# LPC1768.net
KiCad netlist of a schematic drawn in EAGLE
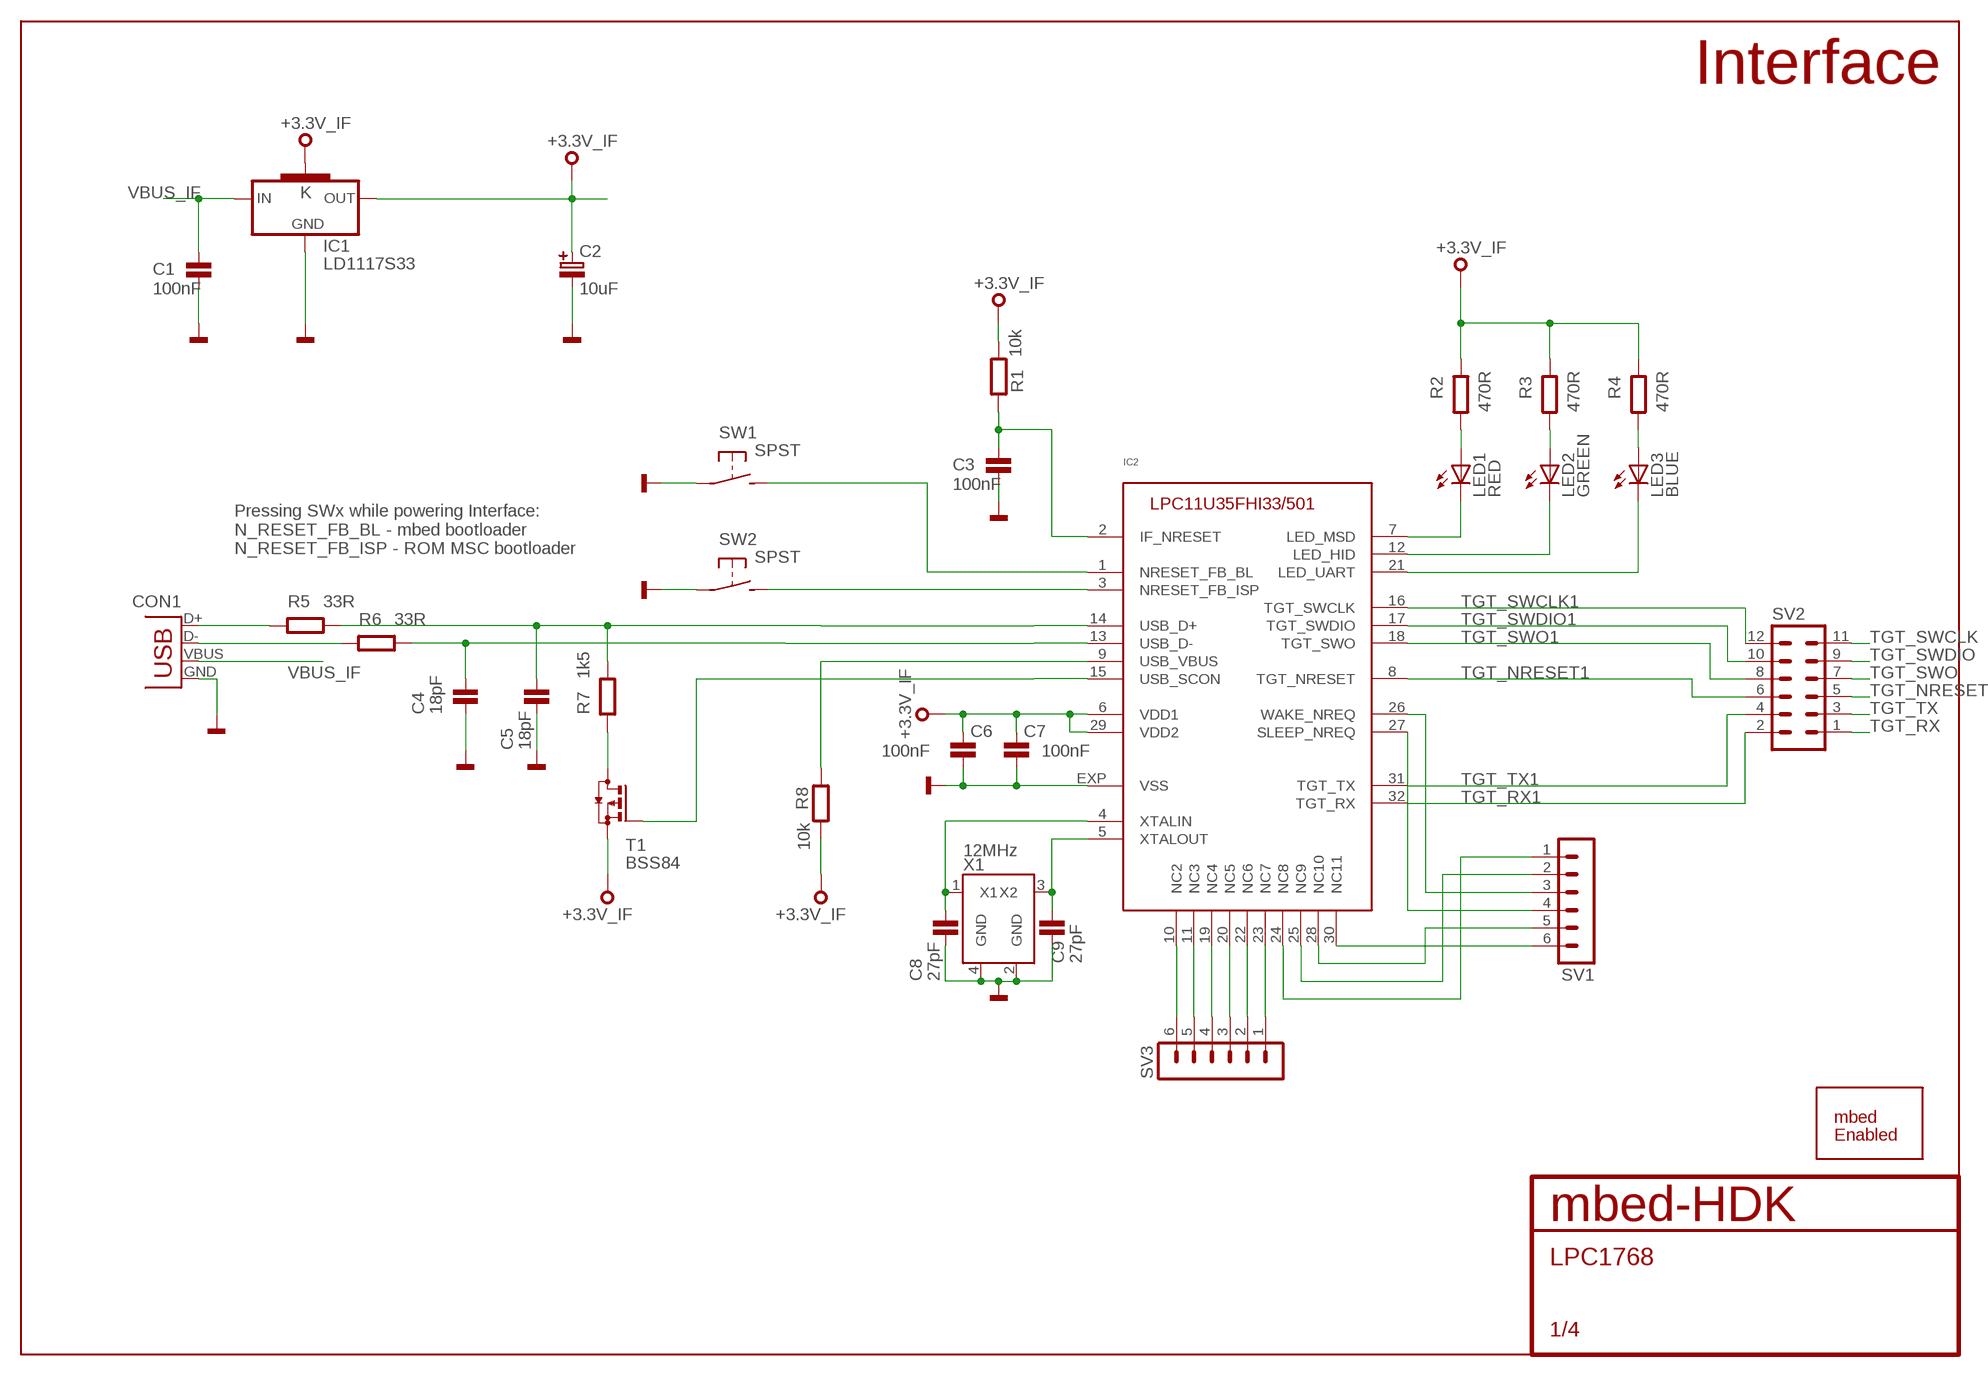
[diagram p0: schematic, sheet 1]
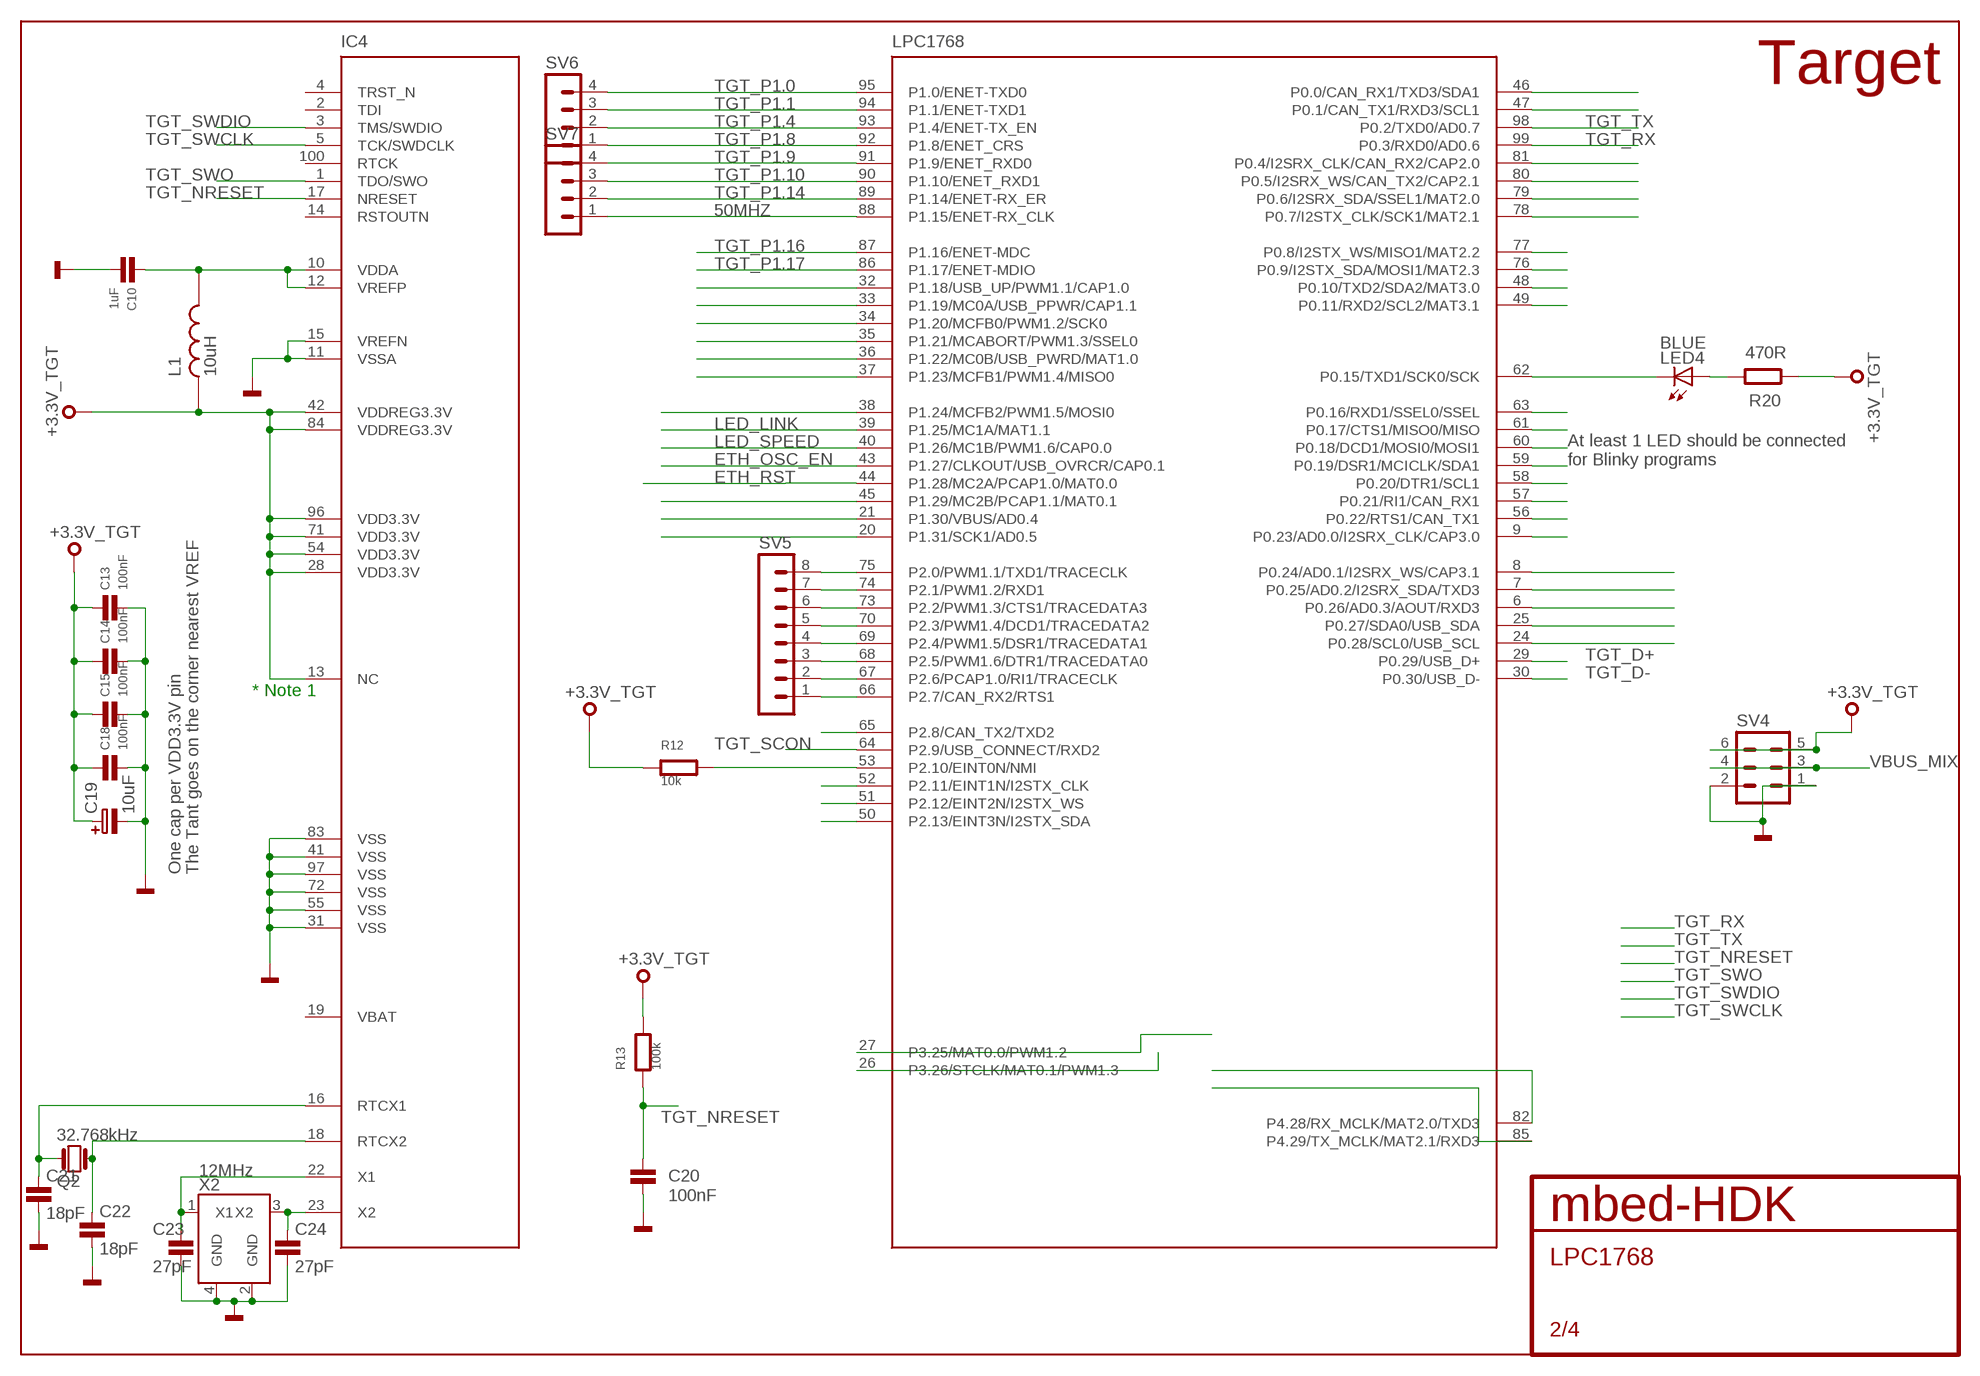
[diagram p1: schematic, sheet 2]
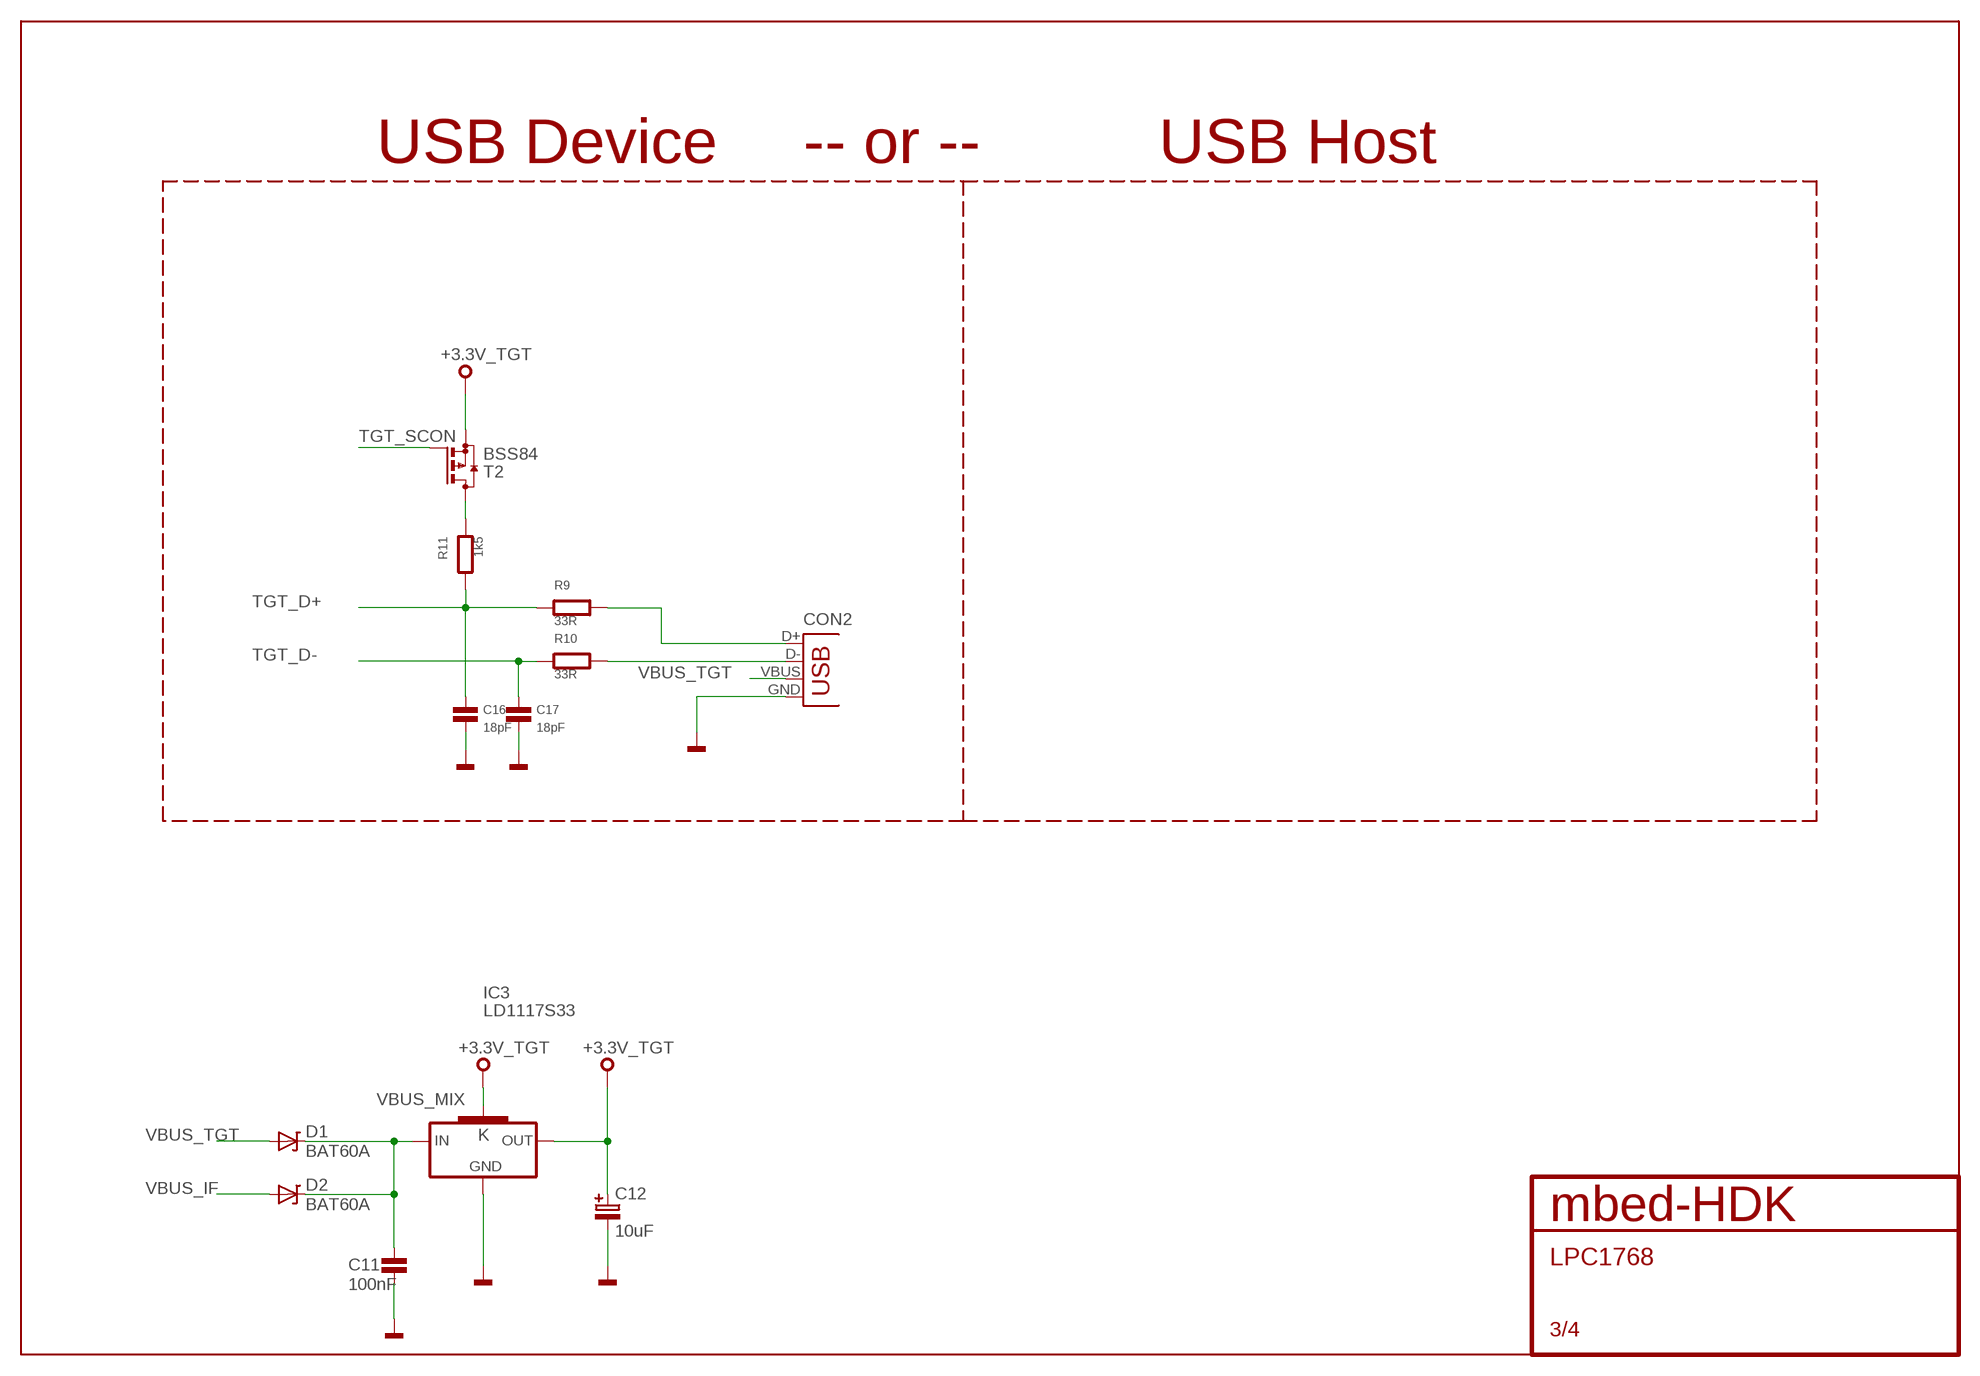
[diagram p2: schematic, sheet 3]
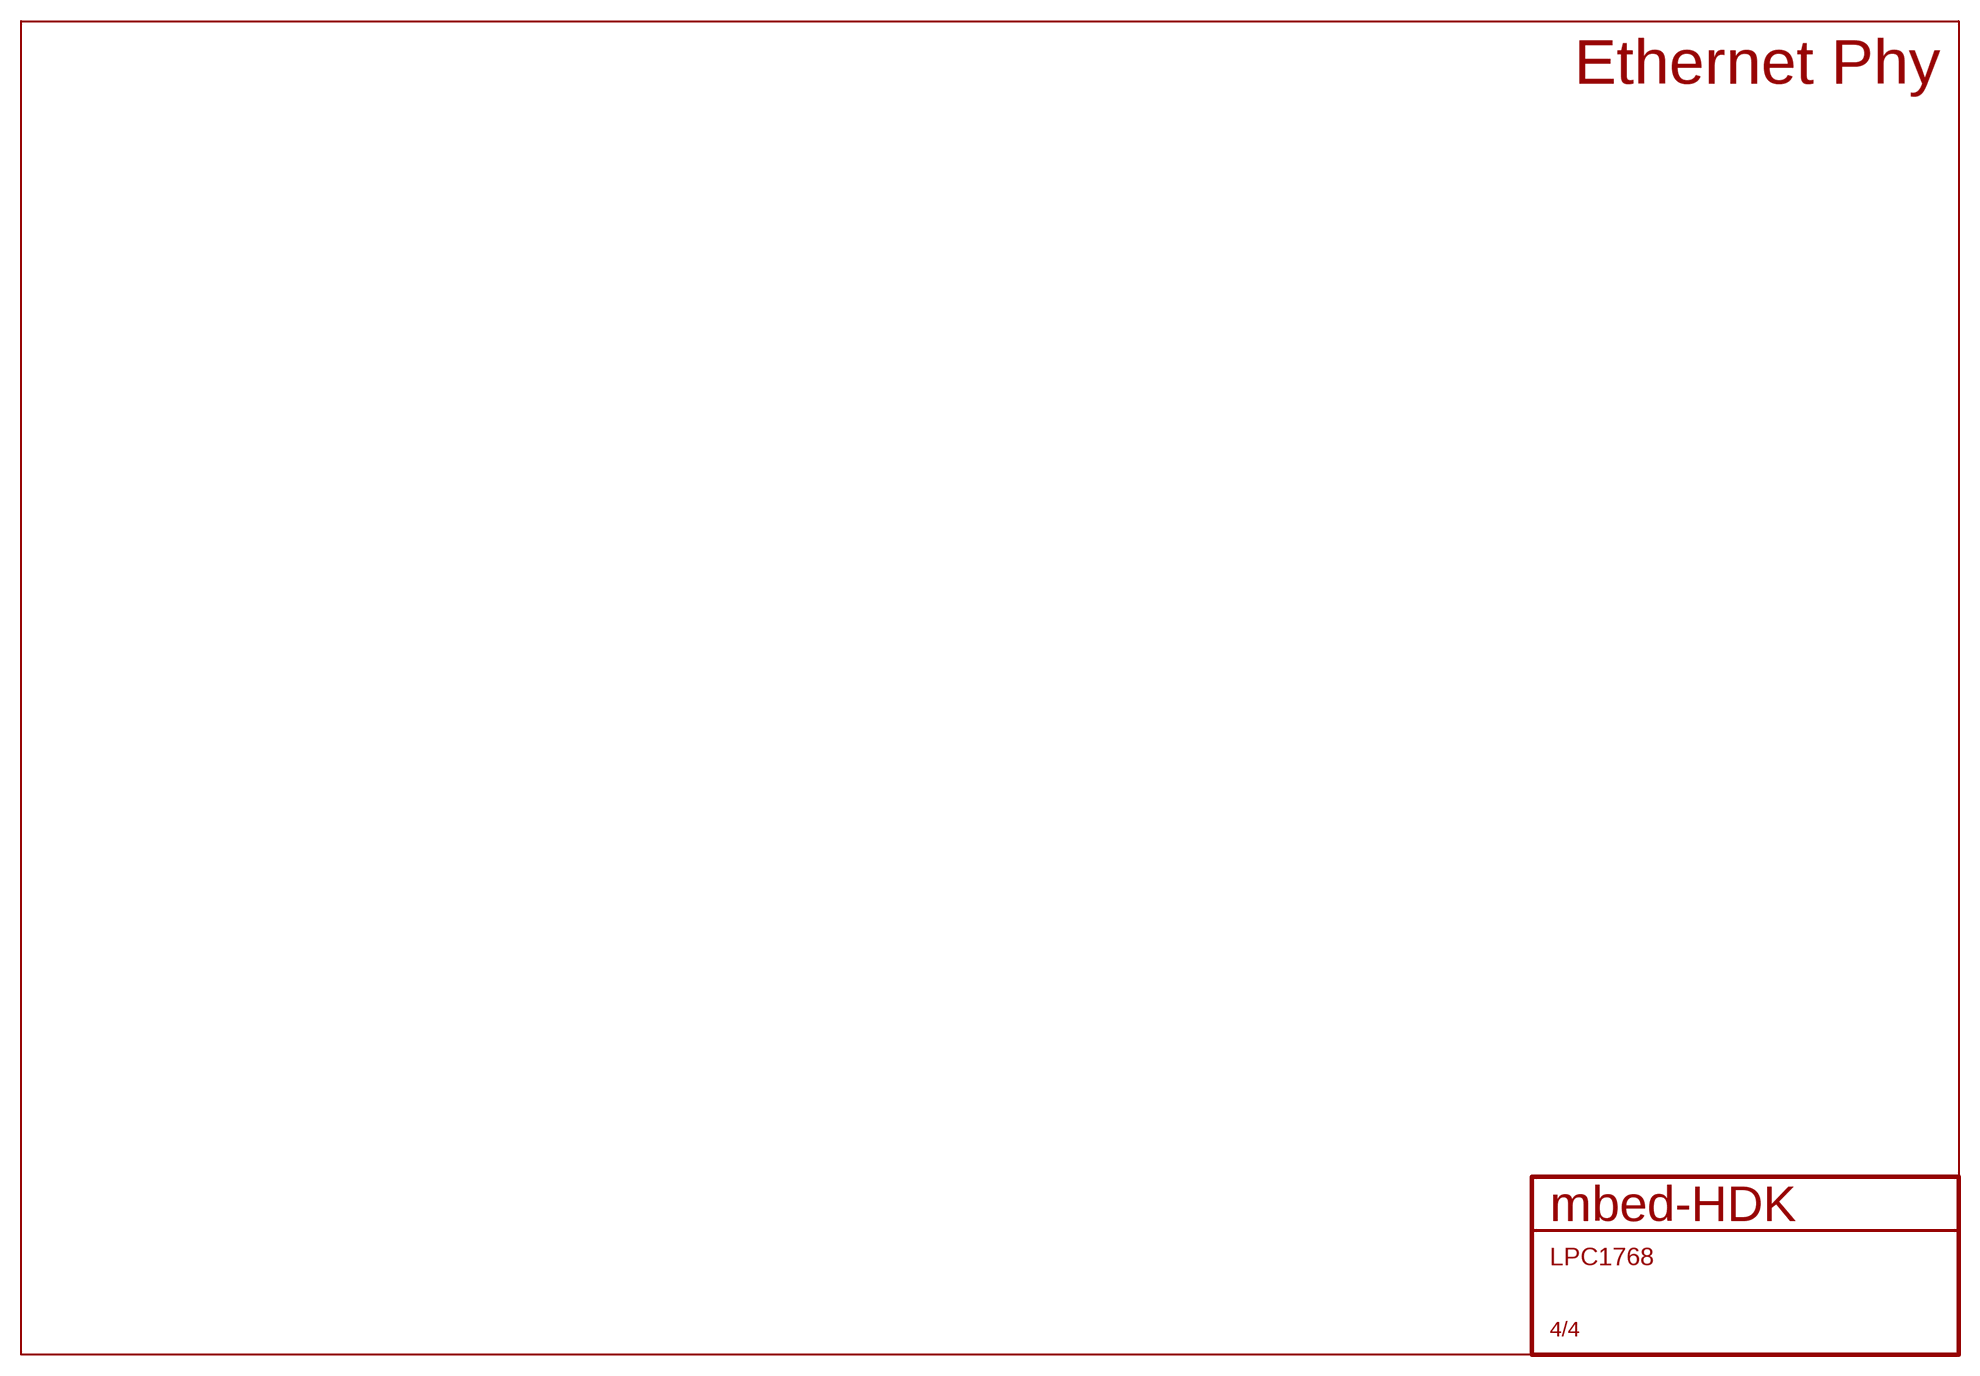
[diagram p3: schematic, sheet 4]

(export (version "E")
  (design (tool "Eeschema 10.0.6"))
  (components
    (comp (ref "C11")
      (value "100nF")
      (footprint "eagle-import:0603")
      (libsource (lib "eagle-import") (part "C0603"))
    )
    (comp (ref "C12")
      (value "10uF")
      (footprint "eagle-import:CASE-B")
      (libsource (lib "eagle-import") (part "C-POLB"))
    )
    (comp (ref "C16")
      (value "18pF")
      (footprint "eagle-import:0603")
      (libsource (lib "eagle-import") (part "C0603"))
    )
    (comp (ref "C17")
      (value "18pF")
      (footprint "eagle-import:0603")
      (libsource (lib "eagle-import") (part "C0603"))
    )
    (comp (ref "CON2")
      (value "USB-MB-S")
      (footprint "eagle-import:USB-MB-S")
      (libsource (lib "eagle-import") (part "USB-MB-S"))
    )
    (comp (ref "D1")
      (value "BAT60A")
      (footprint "eagle-import:BAT60A")
      (libsource (lib "eagle-import") (part "BAT60A"))
    )
    (comp (ref "D2")
      (value "BAT60A")
      (footprint "eagle-import:BAT60A")
      (libsource (lib "eagle-import") (part "BAT60A"))
    )
    (comp (ref "IC3")
      (value "LD1117S33")
      (footprint "eagle-import:SOT223")
      (libsource (lib "eagle-import") (part "LD1117S33"))
    )
    (comp (ref "R9")
      (value "33R")
      (footprint "eagle-import:0603")
      (libsource (lib "eagle-import") (part "R0603"))
    )
    (comp (ref "R10")
      (value "33R")
      (footprint "eagle-import:0603")
      (libsource (lib "eagle-import") (part "R0603"))
    )
    (comp (ref "R11")
      (value "1k5")
      (footprint "eagle-import:0603")
      (libsource (lib "eagle-import") (part "R0603"))
    )
    (comp (ref "T2")
      (value "BSS84")
      (footprint "eagle-import:SOT23")
      (libsource (lib "eagle-import") (part "BSS84"))
    )
    (comp (ref "C10")
      (value "1uF")
      (footprint "eagle-import:0603")
      (libsource (lib "eagle-import") (part "C0603"))
    )
    (comp (ref "C13")
      (value "100nF")
      (footprint "eagle-import:0603")
      (libsource (lib "eagle-import") (part "C0603"))
    )
    (comp (ref "C14")
      (value "100nF")
      (footprint "eagle-import:0603")
      (libsource (lib "eagle-import") (part "C0603"))
    )
    (comp (ref "C15")
      (value "100nF")
      (footprint "eagle-import:0603")
      (libsource (lib "eagle-import") (part "C0603"))
    )
    (comp (ref "C18")
      (value "100nF")
      (footprint "eagle-import:0603")
      (libsource (lib "eagle-import") (part "C0603"))
    )
    (comp (ref "C19")
      (value "10uF")
      (footprint "eagle-import:CASE-B")
      (libsource (lib "eagle-import") (part "C-POLB"))
    )
    (comp (ref "C20")
      (value "100nF")
      (footprint "eagle-import:0603")
      (libsource (lib "eagle-import") (part "C0603"))
    )
    (comp (ref "C21")
      (value "18pF")
      (footprint "eagle-import:0603")
      (libsource (lib "eagle-import") (part "C0603"))
    )
    (comp (ref "C22")
      (value "18pF")
      (footprint "eagle-import:0603")
      (libsource (lib "eagle-import") (part "C0603"))
    )
    (comp (ref "C23")
      (value "27pF")
      (footprint "eagle-import:0603")
      (libsource (lib "eagle-import") (part "C0603"))
    )
    (comp (ref "C24")
      (value "27pF")
      (footprint "eagle-import:0603")
      (libsource (lib "eagle-import") (part "C0603"))
    )
    (comp (ref "IC4")
      (value "LPC1768")
      (footprint "eagle-import:LQFP100")
      (libsource (lib "eagle-import") (part "LPC1768"))
    )
    (comp (ref "L1")
      (value "10uH")
      (footprint "eagle-import:0603")
      (libsource (lib "eagle-import") (part "L"))
    )
    (comp (ref "LED4")
      (value "BLUE")
      (footprint "eagle-import:CHIPLED_0603")
      (libsource (lib "eagle-import") (part "LED0603"))
    )
    (comp (ref "Q2")
      (value "32.768kHz")
      (footprint "eagle-import:FC135")
      (libsource (lib "eagle-import") (part "Q_FC135"))
    )
    (comp (ref "R12")
      (value "10k")
      (footprint "eagle-import:0603")
      (libsource (lib "eagle-import") (part "R0603"))
    )
    (comp (ref "R13")
      (value "100k")
      (footprint "eagle-import:0603")
      (libsource (lib "eagle-import") (part "R0603"))
    )
    (comp (ref "R20")
      (value "470R")
      (footprint "eagle-import:0603")
      (libsource (lib "eagle-import") (part "R0603"))
    )
    (comp (ref "SV4")
      (value "MA03-2")
      (footprint "eagle-import:MA03-2")
      (libsource (lib "eagle-import") (part "MA03-2"))
    )
    (comp (ref "SV5")
      (value "MA08-1")
      (footprint "eagle-import:MA08-1")
      (libsource (lib "eagle-import") (part "MA08-1"))
    )
    (comp (ref "SV6")
      (value "MA04-1")
      (footprint "eagle-import:MA04-1")
      (libsource (lib "eagle-import") (part "MA04-1"))
    )
    (comp (ref "SV7")
      (value "MA04-1")
      (footprint "eagle-import:MA04-1")
      (libsource (lib "eagle-import") (part "MA04-1"))
    )
    (comp (ref "X2")
      (value "12MHz")
      (footprint "eagle-import:OSC_CMD_32_25")
      (libsource (lib "eagle-import") (part "ABM8"))
    )
    (comp (ref "C1")
      (value "100nF")
      (footprint "eagle-import:0603")
      (libsource (lib "eagle-import") (part "C0603"))
    )
    (comp (ref "C2")
      (value "10uF")
      (footprint "eagle-import:CASE-B")
      (libsource (lib "eagle-import") (part "C-POLB"))
    )
    (comp (ref "C3")
      (value "100nF")
      (footprint "eagle-import:0603")
      (libsource (lib "eagle-import") (part "C0603"))
    )
    (comp (ref "C4")
      (value "18pF")
      (footprint "eagle-import:0603")
      (libsource (lib "eagle-import") (part "C0603"))
    )
    (comp (ref "C5")
      (value "18pF")
      (footprint "eagle-import:0603")
      (libsource (lib "eagle-import") (part "C0603"))
    )
    (comp (ref "C6")
      (value "100nF")
      (footprint "eagle-import:0603")
      (libsource (lib "eagle-import") (part "C0603"))
    )
    (comp (ref "C7")
      (value "100nF")
      (footprint "eagle-import:0603")
      (libsource (lib "eagle-import") (part "C0603"))
    )
    (comp (ref "C8")
      (value "27pF")
      (footprint "eagle-import:0603")
      (libsource (lib "eagle-import") (part "C0603"))
    )
    (comp (ref "C9")
      (value "27pF")
      (footprint "eagle-import:0603")
      (libsource (lib "eagle-import") (part "C0603"))
    )
    (comp (ref "CON1")
      (value "USB-MB-S")
      (footprint "eagle-import:USB-MB-S")
      (libsource (lib "eagle-import") (part "USB-MB-S"))
    )
    (comp (ref "IC1")
      (value "LD1117S33")
      (footprint "eagle-import:SOT223")
      (libsource (lib "eagle-import") (part "LD1117S33"))
    )
    (comp (ref "IC2")
      (value "IF-LPC11U35")
      (footprint "eagle-import:HVQFN33")
      (libsource (lib "eagle-import") (part "IF-LPC11U35"))
    )
    (comp (ref "LED1")
      (value "RED")
      (footprint "eagle-import:CHIPLED_0603")
      (libsource (lib "eagle-import") (part "LED0603"))
    )
    (comp (ref "LED2")
      (value "GREEN")
      (footprint "eagle-import:CHIPLED_0603")
      (libsource (lib "eagle-import") (part "LED0603"))
    )
    (comp (ref "LED3")
      (value "BLUE")
      (footprint "eagle-import:CHIPLED_0603")
      (libsource (lib "eagle-import") (part "LED0603"))
    )
    (comp (ref "R1")
      (value "10k")
      (footprint "eagle-import:0603")
      (libsource (lib "eagle-import") (part "R0603"))
    )
    (comp (ref "R2")
      (value "470R")
      (footprint "eagle-import:0603")
      (libsource (lib "eagle-import") (part "R0603"))
    )
    (comp (ref "R3")
      (value "470R")
      (footprint "eagle-import:0603")
      (libsource (lib "eagle-import") (part "R0603"))
    )
    (comp (ref "R4")
      (value "470R")
      (footprint "eagle-import:0603")
      (libsource (lib "eagle-import") (part "R0603"))
    )
    (comp (ref "R5")
      (value "33R")
      (footprint "eagle-import:0603")
      (libsource (lib "eagle-import") (part "R0603"))
    )
    (comp (ref "R6")
      (value "33R")
      (footprint "eagle-import:0603")
      (libsource (lib "eagle-import") (part "R0603"))
    )
    (comp (ref "R7")
      (value "1k5")
      (footprint "eagle-import:0603")
      (libsource (lib "eagle-import") (part "R0603"))
    )
    (comp (ref "R8")
      (value "10k")
      (footprint "eagle-import:0603")
      (libsource (lib "eagle-import") (part "R0603"))
    )
    (comp (ref "SS1")
      (value "MBED-ENABLED-LOGOMEDIUM")
      (footprint "eagle-import:MBED-ENABLED-LOGO-500X500-MIL")
      (libsource (lib "eagle-import") (part "MBED-ENABLED-LOGOMEDIUM"))
    )
    (comp (ref "SV1")
      (value "MA06-1")
      (footprint "eagle-import:MA06-1")
      (libsource (lib "eagle-import") (part "MA06-1"))
    )
    (comp (ref "SV2")
      (value "MA06-2")
      (footprint "eagle-import:MA06-2")
      (libsource (lib "eagle-import") (part "MA06-2"))
    )
    (comp (ref "SV3")
      (value "MA06-1")
      (footprint "eagle-import:MA06-1")
      (libsource (lib "eagle-import") (part "MA06-1"))
    )
    (comp (ref "SW1")
      (value "SPST")
      (footprint "eagle-import:DTSM-32S-B")
      (libsource (lib "eagle-import") (part "SPST"))
    )
    (comp (ref "SW2")
      (value "SPST")
      (footprint "eagle-import:DTSM-32S-B")
      (libsource (lib "eagle-import") (part "SPST"))
    )
    (comp (ref "T1")
      (value "BSS84")
      (footprint "eagle-import:SOT23")
      (libsource (lib "eagle-import") (part "BSS84"))
    )
    (comp (ref "X1")
      (value "12MHz")
      (footprint "eagle-import:OSC_CMD_32_25")
      (libsource (lib "eagle-import") (part "ABM8"))
    )
  )
  (nets
    (net (code "1") (name "+3.3V_IF") (class "Default")
      (node (ref "C2") (pin "1") (pinfunction "1_1") (pintype "passive"))
      (node (ref "C6") (pin "1") (pinfunction "P$1_1") (pintype "passive"))
      (node (ref "C7") (pin "1") (pinfunction "P$1_1") (pintype "passive"))
      (node (ref "IC1") (pin "2") (pinfunction "OUT_2") (pintype "passive"))
      (node (ref "IC1") (pin "4") (pinfunction "K_4") (pintype "passive"))
      (node (ref "IC2") (pin "29") (pinfunction "VDD2_29") (pintype "bidirectional"))
      (node (ref "IC2") (pin "6") (pinfunction "VDD1_6") (pintype "bidirectional"))
      (node (ref "R1") (pin "2") (pinfunction "P$2_2") (pintype "passive"))
      (node (ref "R2") (pin "1") (pinfunction "P$1_1") (pintype "passive"))
      (node (ref "R3") (pin "1") (pinfunction "P$1_1") (pintype "passive"))
      (node (ref "R4") (pin "1") (pinfunction "P$1_1") (pintype "passive"))
      (node (ref "R8") (pin "2") (pinfunction "P$2_2") (pintype "passive"))
      (node (ref "T1") (pin "2") (pinfunction "S_2") (pintype "passive"))
    )
    (net (code "2") (name "+3.3V_TGT") (class "Default")
      (node (ref "C12") (pin "1") (pinfunction "1_1") (pintype "passive"))
      (node (ref "C13") (pin "1") (pinfunction "P$1_1") (pintype "passive"))
      (node (ref "C14") (pin "1") (pinfunction "P$1_1") (pintype "passive"))
      (node (ref "C15") (pin "1") (pinfunction "P$1_1") (pintype "passive"))
      (node (ref "C18") (pin "1") (pinfunction "P$1_1") (pintype "passive"))
      (node (ref "C19") (pin "1") (pinfunction "1_1") (pintype "passive"))
      (node (ref "IC3") (pin "2") (pinfunction "OUT_2") (pintype "passive"))
      (node (ref "IC3") (pin "4") (pinfunction "K_4") (pintype "passive"))
      (node (ref "IC4") (pin "13") (pinfunction "NC_13") (pintype "bidirectional"))
      (node (ref "IC4") (pin "28") (pinfunction "VDD3.3V_28") (pintype "bidirectional"))
      (node (ref "IC4") (pin "42") (pinfunction "VDDREG3.3V_42") (pintype "bidirectional"))
      (node (ref "IC4") (pin "54") (pinfunction "VDD3.3V_54") (pintype "bidirectional"))
      (node (ref "IC4") (pin "71") (pinfunction "VDD3.3V_71") (pintype "bidirectional"))
      (node (ref "IC4") (pin "84") (pinfunction "VDDREG3.3V_84") (pintype "bidirectional"))
      (node (ref "IC4") (pin "96") (pinfunction "VDD3.3V_96") (pintype "bidirectional"))
      (node (ref "L1") (pin "1") (pinfunction "P$1_1") (pintype "bidirectional"))
      (node (ref "R12") (pin "1") (pinfunction "P$1_1") (pintype "passive"))
      (node (ref "R13") (pin "2") (pinfunction "P$2_2") (pintype "passive"))
      (node (ref "R20") (pin "1") (pinfunction "P$1_1") (pintype "passive"))
      (node (ref "SV4") (pin "5") (pinfunction "5_5") (pintype "passive"))
      (node (ref "SV4") (pin "6") (pinfunction "6_6") (pintype "passive"))
      (node (ref "T2") (pin "2") (pinfunction "S_2") (pintype "passive"))
    )
    (net (code "3") (name "50MHZ") (class "Default")
      (node (ref "IC4") (pin "88") (pinfunction "P1.15/ENET-RX_CLK_88") (pintype "bidirectional"))
      (node (ref "SV7") (pin "1") (pinfunction "1_1") (pintype "passive"))
    )
    (net (code "4") (name "ETH_OSC_EN") (class "Default")
      (node (ref "IC4") (pin "43") (pinfunction "P1.27/CLKOUT/USB_OVRCR/CAP0.1_43") (pintype "bidirectional"))
    )
    (net (code "5") (name "ETH_RST") (class "Default")
      (node (ref "IC4") (pin "44") (pinfunction "P1.28/MC2A/PCAP1.0/MAT0.0_44") (pintype "bidirectional"))
    )
    (net (code "6") (name "GND") (class "Default")
      (node (ref "C1") (pin "2") (pinfunction "P$2_2") (pintype "passive"))
      (node (ref "C10") (pin "2") (pinfunction "P$2_2") (pintype "passive"))
      (node (ref "C11") (pin "2") (pinfunction "P$2_2") (pintype "passive"))
      (node (ref "C12") (pin "2") (pinfunction "2_2") (pintype "passive"))
      (node (ref "C13") (pin "2") (pinfunction "P$2_2") (pintype "passive"))
      (node (ref "C14") (pin "2") (pinfunction "P$2_2") (pintype "passive"))
      (node (ref "C15") (pin "2") (pinfunction "P$2_2") (pintype "passive"))
      (node (ref "C16") (pin "2") (pinfunction "P$2_2") (pintype "passive"))
      (node (ref "C17") (pin "2") (pinfunction "P$2_2") (pintype "passive"))
      (node (ref "C18") (pin "2") (pinfunction "P$2_2") (pintype "passive"))
      (node (ref "C19") (pin "2") (pinfunction "2_2") (pintype "passive"))
      (node (ref "C2") (pin "2") (pinfunction "2_2") (pintype "passive"))
      (node (ref "C20") (pin "1") (pinfunction "P$1_1") (pintype "passive"))
      (node (ref "C21") (pin "1") (pinfunction "P$1_1") (pintype "passive"))
      (node (ref "C22") (pin "1") (pinfunction "P$1_1") (pintype "passive"))
      (node (ref "C23") (pin "1") (pinfunction "P$1_1") (pintype "passive"))
      (node (ref "C24") (pin "1") (pinfunction "P$1_1") (pintype "passive"))
      (node (ref "C3") (pin "2") (pinfunction "P$2_2") (pintype "passive"))
      (node (ref "C4") (pin "2") (pinfunction "P$2_2") (pintype "passive"))
      (node (ref "C5") (pin "2") (pinfunction "P$2_2") (pintype "passive"))
      (node (ref "C6") (pin "2") (pinfunction "P$2_2") (pintype "passive"))
      (node (ref "C7") (pin "2") (pinfunction "P$2_2") (pintype "passive"))
      (node (ref "C8") (pin "2") (pinfunction "P$2_2") (pintype "passive"))
      (node (ref "C9") (pin "2") (pinfunction "P$2_2") (pintype "passive"))
      (node (ref "CON1") (pin "GND") (pinfunction "GND_GND") (pintype "bidirectional"))
      (node (ref "CON2") (pin "GND") (pinfunction "GND_GND") (pintype "bidirectional"))
      (node (ref "IC1") (pin "1") (pinfunction "GND_1") (pintype "input"))
      (node (ref "IC2") (pin "EXP") (pinfunction "VSS_EXP") (pintype "bidirectional"))
      (node (ref "IC3") (pin "1") (pinfunction "GND_1") (pintype "input"))
      (node (ref "IC4") (pin "11") (pinfunction "VSSA_11") (pintype "bidirectional"))
      (node (ref "IC4") (pin "15") (pinfunction "VREFN_15") (pintype "bidirectional"))
      (node (ref "IC4") (pin "31") (pinfunction "VSS_31") (pintype "bidirectional"))
      (node (ref "IC4") (pin "41") (pinfunction "VSS_41") (pintype "bidirectional"))
      (node (ref "IC4") (pin "55") (pinfunction "VSS_55") (pintype "bidirectional"))
      (node (ref "IC4") (pin "72") (pinfunction "VSS_72") (pintype "bidirectional"))
      (node (ref "IC4") (pin "83") (pinfunction "VSS_83") (pintype "bidirectional"))
      (node (ref "IC4") (pin "97") (pinfunction "VSS_97") (pintype "bidirectional"))
      (node (ref "SV4") (pin "1") (pinfunction "1_1") (pintype "passive"))
      (node (ref "SV4") (pin "2") (pinfunction "2_2") (pintype "passive"))
      (node (ref "SW1") (pin "P$1") (pinfunction "P_P$1") (pintype "passive"))
      (node (ref "SW2") (pin "P$1") (pinfunction "P_P$1") (pintype "passive"))
      (node (ref "X1") (pin "2") (pinfunction "GND_2") (pintype "bidirectional"))
      (node (ref "X1") (pin "4") (pinfunction "GND_4") (pintype "bidirectional"))
      (node (ref "X2") (pin "2") (pinfunction "GND_2") (pintype "bidirectional"))
      (node (ref "X2") (pin "4") (pinfunction "GND_4") (pintype "bidirectional"))
    )
    (net (code "7") (name "LED_LINK") (class "Default")
      (node (ref "IC4") (pin "39") (pinfunction "P1.25/MC1A/MAT1.1_39") (pintype "bidirectional"))
    )
    (net (code "8") (name "LED_SPEED") (class "Default")
      (node (ref "IC4") (pin "40") (pinfunction "P1.26/MC1B/PWM1.6/CAP0.0_40") (pintype "bidirectional"))
    )
    (net (code "9") (name "Net-(C3-P$1)") (class "Default")
      (node (ref "C3") (pin "1") (pinfunction "P$1_1") (pintype "passive"))
      (node (ref "IC2") (pin "2") (pinfunction "IF_NRESET_2") (pintype "bidirectional"))
      (node (ref "R1") (pin "1") (pinfunction "P$1_1") (pintype "passive"))
    )
    (net (code "10") (name "Net-(C4-P$1)") (class "Default")
      (node (ref "C4") (pin "1") (pinfunction "P$1_1") (pintype "passive"))
      (node (ref "IC2") (pin "13") (pinfunction "USB_D-_13") (pintype "bidirectional"))
      (node (ref "R6") (pin "2") (pinfunction "P$2_2") (pintype "passive"))
    )
    (net (code "11") (name "Net-(C5-P$1)") (class "Default")
      (node (ref "C5") (pin "1") (pinfunction "P$1_1") (pintype "passive"))
      (node (ref "IC2") (pin "14") (pinfunction "USB_D+_14") (pintype "bidirectional"))
      (node (ref "R5") (pin "2") (pinfunction "P$2_2") (pintype "passive"))
      (node (ref "R7") (pin "2") (pinfunction "P$2_2") (pintype "passive"))
    )
    (net (code "12") (name "Net-(C8-P$1)") (class "Default")
      (node (ref "C8") (pin "1") (pinfunction "P$1_1") (pintype "passive"))
      (node (ref "IC2") (pin "4") (pinfunction "XTALIN_4") (pintype "bidirectional"))
      (node (ref "X1") (pin "1") (pinfunction "X1_1") (pintype "bidirectional"))
    )
    (net (code "13") (name "Net-(C9-P$1)") (class "Default")
      (node (ref "C9") (pin "1") (pinfunction "P$1_1") (pintype "passive"))
      (node (ref "IC2") (pin "5") (pinfunction "XTALOUT_5") (pintype "bidirectional"))
      (node (ref "X1") (pin "3") (pinfunction "X2_3") (pintype "bidirectional"))
    )
    (net (code "14") (name "Net-(C10-P$1)") (class "Default")
      (node (ref "C10") (pin "1") (pinfunction "P$1_1") (pintype "passive"))
      (node (ref "IC4") (pin "10") (pinfunction "VDDA_10") (pintype "bidirectional"))
      (node (ref "IC4") (pin "12") (pinfunction "VREFP_12") (pintype "bidirectional"))
      (node (ref "L1") (pin "2") (pinfunction "P$2_2") (pintype "bidirectional"))
    )
    (net (code "15") (name "Net-(C21-P$2)") (class "Default")
      (node (ref "C21") (pin "2") (pinfunction "P$2_2") (pintype "passive"))
      (node (ref "IC4") (pin "16") (pinfunction "RTCX1_16") (pintype "bidirectional"))
      (node (ref "Q2") (pin "X2") (pinfunction "2_X2") (pintype "passive"))
    )
    (net (code "16") (name "Net-(C22-P$2)") (class "Default")
      (node (ref "C22") (pin "2") (pinfunction "P$2_2") (pintype "passive"))
      (node (ref "IC4") (pin "18") (pinfunction "RTCX2_18") (pintype "bidirectional"))
      (node (ref "Q2") (pin "X1") (pinfunction "1_X1") (pintype "passive"))
    )
    (net (code "17") (name "Net-(C23-P$2)") (class "Default")
      (node (ref "C23") (pin "2") (pinfunction "P$2_2") (pintype "passive"))
      (node (ref "IC4") (pin "22") (pinfunction "X1_22") (pintype "bidirectional"))
      (node (ref "X2") (pin "1") (pinfunction "X1_1") (pintype "bidirectional"))
    )
    (net (code "18") (name "Net-(C24-P$2)") (class "Default")
      (node (ref "C24") (pin "2") (pinfunction "P$2_2") (pintype "passive"))
      (node (ref "IC4") (pin "23") (pinfunction "X2_23") (pintype "bidirectional"))
      (node (ref "X2") (pin "3") (pinfunction "X2_3") (pintype "bidirectional"))
    )
    (net (code "19") (name "Net-(IC2-LED_HID)") (class "Default")
      (node (ref "IC2") (pin "12") (pinfunction "LED_HID_12") (pintype "bidirectional"))
      (node (ref "LED2") (pin "C") (pinfunction "C_C") (pintype "passive"))
    )
    (net (code "20") (name "Net-(IC2-LED_MSD)") (class "Default")
      (node (ref "IC2") (pin "7") (pinfunction "LED_MSD_7") (pintype "bidirectional"))
      (node (ref "LED1") (pin "C") (pinfunction "C_C") (pintype "passive"))
    )
    (net (code "21") (name "Net-(IC2-LED_UART)") (class "Default")
      (node (ref "IC2") (pin "21") (pinfunction "LED_UART_21") (pintype "bidirectional"))
      (node (ref "LED3") (pin "C") (pinfunction "C_C") (pintype "passive"))
    )
    (net (code "22") (name "Net-(IC2-NC2)") (class "Default")
      (node (ref "IC2") (pin "10") (pinfunction "NC2_10") (pintype "bidirectional"))
      (node (ref "SV3") (pin "6") (pinfunction "6_6") (pintype "passive"))
    )
    (net (code "23") (name "Net-(IC2-NC3)") (class "Default")
      (node (ref "IC2") (pin "11") (pinfunction "NC3_11") (pintype "bidirectional"))
      (node (ref "SV3") (pin "5") (pinfunction "5_5") (pintype "passive"))
    )
    (net (code "24") (name "Net-(IC2-NC4)") (class "Default")
      (node (ref "IC2") (pin "19") (pinfunction "NC4_19") (pintype "bidirectional"))
      (node (ref "SV3") (pin "4") (pinfunction "4_4") (pintype "passive"))
    )
    (net (code "25") (name "Net-(IC2-NC5)") (class "Default")
      (node (ref "IC2") (pin "20") (pinfunction "NC5_20") (pintype "bidirectional"))
      (node (ref "SV3") (pin "3") (pinfunction "3_3") (pintype "passive"))
    )
    (net (code "26") (name "Net-(IC2-NC6)") (class "Default")
      (node (ref "IC2") (pin "22") (pinfunction "NC6_22") (pintype "bidirectional"))
      (node (ref "SV3") (pin "2") (pinfunction "2_2") (pintype "passive"))
    )
    (net (code "27") (name "Net-(IC2-NC7)") (class "Default")
      (node (ref "IC2") (pin "23") (pinfunction "NC7_23") (pintype "bidirectional"))
      (node (ref "SV3") (pin "1") (pinfunction "1_1") (pintype "passive"))
    )
    (net (code "28") (name "Net-(IC2-NC8)") (class "Default")
      (node (ref "IC2") (pin "24") (pinfunction "NC8_24") (pintype "bidirectional"))
      (node (ref "SV1") (pin "1") (pinfunction "1_1") (pintype "passive"))
    )
    (net (code "29") (name "Net-(IC2-NC9)") (class "Default")
      (node (ref "IC2") (pin "25") (pinfunction "NC9_25") (pintype "bidirectional"))
      (node (ref "SV1") (pin "2") (pinfunction "2_2") (pintype "passive"))
    )
    (net (code "30") (name "Net-(IC2-NC10)") (class "Default")
      (node (ref "IC2") (pin "28") (pinfunction "NC10_28") (pintype "bidirectional"))
      (node (ref "SV1") (pin "5") (pinfunction "5_5") (pintype "passive"))
    )
    (net (code "31") (name "Net-(IC2-NC11)") (class "Default")
      (node (ref "IC2") (pin "30") (pinfunction "NC11_30") (pintype "bidirectional"))
      (node (ref "SV1") (pin "6") (pinfunction "6_6") (pintype "passive"))
    )
    (net (code "32") (name "Net-(IC2-NRESET_FB_BL)") (class "Default")
      (node (ref "IC2") (pin "1") (pinfunction "NRESET_FB_BL_1") (pintype "bidirectional"))
      (node (ref "SW1") (pin "P$2") (pinfunction "S_P$2") (pintype "passive"))
    )
    (net (code "33") (name "Net-(IC2-NRESET_FB_ISP)") (class "Default")
      (node (ref "IC2") (pin "3") (pinfunction "NRESET_FB_ISP_3") (pintype "bidirectional"))
      (node (ref "SW2") (pin "P$2") (pinfunction "S_P$2") (pintype "passive"))
    )
    (net (code "34") (name "Net-(IC2-SLEEP_NREQ)") (class "Default")
      (node (ref "IC2") (pin "27") (pinfunction "SLEEP_NREQ_27") (pintype "bidirectional"))
      (node (ref "SV1") (pin "4") (pinfunction "4_4") (pintype "passive"))
    )
    (net (code "35") (name "Net-(IC2-USB_SCON)") (class "Default")
      (node (ref "IC2") (pin "15") (pinfunction "USB_SCON_15") (pintype "bidirectional"))
      (node (ref "T1") (pin "1") (pinfunction "G_1") (pintype "passive"))
    )
    (net (code "36") (name "Net-(IC2-USB_VBUS)") (class "Default")
      (node (ref "IC2") (pin "9") (pinfunction "USB_VBUS_9") (pintype "bidirectional"))
      (node (ref "R8") (pin "1") (pinfunction "P$1_1") (pintype "passive"))
    )
    (net (code "37") (name "Net-(IC2-WAKE_NREQ)") (class "Default")
      (node (ref "IC2") (pin "26") (pinfunction "WAKE_NREQ_26") (pintype "bidirectional"))
      (node (ref "SV1") (pin "3") (pinfunction "3_3") (pintype "passive"))
    )
    (net (code "38") (name "Net-(IC4-P0.15{slash}TXD1{slash}SCK0{slash}SCK)") (class "Default")
      (node (ref "IC4") (pin "62") (pinfunction "P0.15/TXD1/SCK0/SCK_62") (pintype "bidirectional"))
      (node (ref "LED4") (pin "C") (pinfunction "C_C") (pintype "passive"))
    )
    (net (code "39") (name "Net-(IC4-P2.0{slash}PWM1.1{slash}TXD1{slash}TRACECLK)") (class "Default")
      (node (ref "IC4") (pin "75") (pinfunction "P2.0/PWM1.1/TXD1/TRACECLK_75") (pintype "bidirectional"))
      (node (ref "SV5") (pin "8") (pinfunction "8_8") (pintype "passive"))
    )
    (net (code "40") (name "Net-(IC4-P2.1{slash}PWM1.2{slash}RXD1)") (class "Default")
      (node (ref "IC4") (pin "74") (pinfunction "P2.1/PWM1.2/RXD1_74") (pintype "bidirectional"))
      (node (ref "SV5") (pin "7") (pinfunction "7_7") (pintype "passive"))
    )
    (net (code "41") (name "Net-(IC4-P2.2{slash}PWM1.3{slash}CTS1{slash}TRACEDATA3)") (class "Default")
      (node (ref "IC4") (pin "73") (pinfunction "P2.2/PWM1.3/CTS1/TRACEDATA3_73") (pintype "bidirectional"))
      (node (ref "SV5") (pin "6") (pinfunction "6_6") (pintype "passive"))
    )
    (net (code "42") (name "Net-(IC4-P2.3{slash}PWM1.4{slash}DCD1{slash}TRACEDATA2)") (class "Default")
      (node (ref "IC4") (pin "70") (pinfunction "P2.3/PWM1.4/DCD1/TRACEDATA2_70") (pintype "bidirectional"))
      (node (ref "SV5") (pin "5") (pinfunction "5_5") (pintype "passive"))
    )
    (net (code "43") (name "Net-(IC4-P2.4{slash}PWM1.5{slash}DSR1{slash}TRACEDATA1)") (class "Default")
      (node (ref "IC4") (pin "69") (pinfunction "P2.4/PWM1.5/DSR1/TRACEDATA1_69") (pintype "bidirectional"))
      (node (ref "SV5") (pin "4") (pinfunction "4_4") (pintype "passive"))
    )
    (net (code "44") (name "Net-(IC4-P2.5{slash}PWM1.6{slash}DTR1{slash}TRACEDATA0)") (class "Default")
      (node (ref "IC4") (pin "68") (pinfunction "P2.5/PWM1.6/DTR1/TRACEDATA0_68") (pintype "bidirectional"))
      (node (ref "SV5") (pin "3") (pinfunction "3_3") (pintype "passive"))
    )
    (net (code "45") (name "Net-(IC4-P2.6{slash}PCAP1.0{slash}RI1{slash}TRACECLK)") (class "Default")
      (node (ref "IC4") (pin "67") (pinfunction "P2.6/PCAP1.0/RI1/TRACECLK_67") (pintype "bidirectional"))
      (node (ref "SV5") (pin "2") (pinfunction "2_2") (pintype "passive"))
    )
    (net (code "46") (name "Net-(IC4-P2.7{slash}CAN_RX2{slash}RTS1)") (class "Default")
      (node (ref "IC4") (pin "66") (pinfunction "P2.7/CAN_RX2/RTS1_66") (pintype "bidirectional"))
      (node (ref "SV5") (pin "1") (pinfunction "1_1") (pintype "passive"))
    )
    (net (code "47") (name "Net-(IC4-P2.10{slash}EINT0N{slash}NMI)") (class "Default")
      (node (ref "IC4") (pin "53") (pinfunction "P2.10/EINT0N/NMI_53") (pintype "bidirectional"))
      (node (ref "R12") (pin "2") (pinfunction "P$2_2") (pintype "passive"))
    )
    (net (code "48") (name "Net-(R2-P$2)") (class "Default")
      (node (ref "LED1") (pin "A") (pinfunction "A_A") (pintype "passive"))
      (node (ref "R2") (pin "2") (pinfunction "P$2_2") (pintype "passive"))
    )
    (net (code "49") (name "Net-(R3-P$2)") (class "Default")
      (node (ref "LED2") (pin "A") (pinfunction "A_A") (pintype "passive"))
      (node (ref "R3") (pin "2") (pinfunction "P$2_2") (pintype "passive"))
    )
    (net (code "50") (name "Net-(R4-P$2)") (class "Default")
      (node (ref "LED3") (pin "A") (pinfunction "A_A") (pintype "passive"))
      (node (ref "R4") (pin "2") (pinfunction "P$2_2") (pintype "passive"))
    )
    (net (code "51") (name "Net-(R5-P$1)") (class "Default")
      (node (ref "CON1") (pin "D+") (pinfunction "D+_D+") (pintype "bidirectional"))
      (node (ref "R5") (pin "1") (pinfunction "P$1_1") (pintype "passive"))
    )
    (net (code "52") (name "Net-(R6-P$1)") (class "Default")
      (node (ref "CON1") (pin "D-") (pinfunction "D-_D-") (pintype "bidirectional"))
      (node (ref "R6") (pin "1") (pinfunction "P$1_1") (pintype "passive"))
    )
    (net (code "53") (name "Net-(R7-P$1)") (class "Default")
      (node (ref "R7") (pin "1") (pinfunction "P$1_1") (pintype "passive"))
      (node (ref "T1") (pin "3") (pinfunction "D_3") (pintype "passive"))
    )
    (net (code "54") (name "Net-(R9-P$2)") (class "Default")
      (node (ref "CON2") (pin "D+") (pinfunction "D+_D+") (pintype "bidirectional"))
      (node (ref "R9") (pin "2") (pinfunction "P$2_2") (pintype "passive"))
    )
    (net (code "55") (name "Net-(R10-P$2)") (class "Default")
      (node (ref "CON2") (pin "D-") (pinfunction "D-_D-") (pintype "bidirectional"))
      (node (ref "R10") (pin "2") (pinfunction "P$2_2") (pintype "passive"))
    )
    (net (code "56") (name "Net-(R11-P$1)") (class "Default")
      (node (ref "R11") (pin "1") (pinfunction "P$1_1") (pintype "passive"))
      (node (ref "T2") (pin "3") (pinfunction "D_3") (pintype "passive"))
    )
    (net (code "57") (name "Net-(R20-P$2)") (class "Default")
      (node (ref "LED4") (pin "A") (pinfunction "A_A") (pintype "passive"))
      (node (ref "R20") (pin "2") (pinfunction "P$2_2") (pintype "passive"))
    )
    (net (code "58") (name "TGT_D+") (class "Default")
      (node (ref "C16") (pin "1") (pinfunction "P$1_1") (pintype "passive"))
      (node (ref "IC4") (pin "29") (pinfunction "P0.29/USB_D+_29") (pintype "bidirectional"))
      (node (ref "R11") (pin "2") (pinfunction "P$2_2") (pintype "passive"))
      (node (ref "R9") (pin "1") (pinfunction "P$1_1") (pintype "passive"))
    )
    (net (code "59") (name "TGT_D-") (class "Default")
      (node (ref "C17") (pin "1") (pinfunction "P$1_1") (pintype "passive"))
      (node (ref "IC4") (pin "30") (pinfunction "P0.30/USB_D-_30") (pintype "bidirectional"))
      (node (ref "R10") (pin "1") (pinfunction "P$1_1") (pintype "passive"))
    )
    (net (code "60") (name "TGT_NRESET") (class "Default")
      (node (ref "C20") (pin "2") (pinfunction "P$2_2") (pintype "passive"))
      (node (ref "IC4") (pin "17") (pinfunction "NRESET_17") (pintype "bidirectional"))
      (node (ref "R13") (pin "1") (pinfunction "P$1_1") (pintype "passive"))
      (node (ref "SV2") (pin "5") (pinfunction "5_5") (pintype "passive"))
    )
    (net (code "61") (name "TGT_NRESET1") (class "Default")
      (node (ref "IC2") (pin "8") (pinfunction "TGT_NRESET_8") (pintype "bidirectional"))
      (node (ref "SV2") (pin "6") (pinfunction "6_6") (pintype "passive"))
    )
    (net (code "62") (name "TGT_P1.0") (class "Default")
      (node (ref "IC4") (pin "95") (pinfunction "P1.0/ENET-TXD0_95") (pintype "bidirectional"))
      (node (ref "SV6") (pin "4") (pinfunction "4_4") (pintype "passive"))
    )
    (net (code "63") (name "TGT_P1.1") (class "Default")
      (node (ref "IC4") (pin "94") (pinfunction "P1.1/ENET-TXD1_94") (pintype "bidirectional"))
      (node (ref "SV6") (pin "3") (pinfunction "3_3") (pintype "passive"))
    )
    (net (code "64") (name "TGT_P1.4") (class "Default")
      (node (ref "IC4") (pin "93") (pinfunction "P1.4/ENET-TX_EN_93") (pintype "bidirectional"))
      (node (ref "SV6") (pin "2") (pinfunction "2_2") (pintype "passive"))
    )
    (net (code "65") (name "TGT_P1.8") (class "Default")
      (node (ref "IC4") (pin "92") (pinfunction "P1.8/ENET_CRS_92") (pintype "bidirectional"))
      (node (ref "SV6") (pin "1") (pinfunction "1_1") (pintype "passive"))
    )
    (net (code "66") (name "TGT_P1.9") (class "Default")
      (node (ref "IC4") (pin "91") (pinfunction "P1.9/ENET_RXD0_91") (pintype "bidirectional"))
      (node (ref "SV7") (pin "4") (pinfunction "4_4") (pintype "passive"))
    )
    (net (code "67") (name "TGT_P1.10") (class "Default")
      (node (ref "IC4") (pin "90") (pinfunction "P1.10/ENET_RXD1_90") (pintype "bidirectional"))
      (node (ref "SV7") (pin "3") (pinfunction "3_3") (pintype "passive"))
    )
    (net (code "68") (name "TGT_P1.14") (class "Default")
      (node (ref "IC4") (pin "89") (pinfunction "P1.14/ENET-RX_ER_89") (pintype "bidirectional"))
      (node (ref "SV7") (pin "2") (pinfunction "2_2") (pintype "passive"))
    )
    (net (code "69") (name "TGT_P1.16") (class "Default")
      (node (ref "IC4") (pin "87") (pinfunction "P1.16/ENET-MDC_87") (pintype "bidirectional"))
    )
    (net (code "70") (name "TGT_P1.17") (class "Default")
      (node (ref "IC4") (pin "86") (pinfunction "P1.17/ENET-MDIO_86") (pintype "bidirectional"))
    )
    (net (code "71") (name "TGT_RX") (class "Default")
      (node (ref "IC4") (pin "99") (pinfunction "P0.3/RXD0/AD0.6_99") (pintype "bidirectional"))
      (node (ref "SV2") (pin "1") (pinfunction "1_1") (pintype "passive"))
    )
    (net (code "72") (name "TGT_RX1") (class "Default")
      (node (ref "IC2") (pin "32") (pinfunction "TGT_RX_32") (pintype "bidirectional"))
      (node (ref "SV2") (pin "2") (pinfunction "2_2") (pintype "passive"))
    )
    (net (code "73") (name "TGT_SCON") (class "Default")
      (node (ref "IC4") (pin "64") (pinfunction "P2.9/USB_CONNECT/RXD2_64") (pintype "bidirectional"))
      (node (ref "T2") (pin "1") (pinfunction "G_1") (pintype "passive"))
    )
    (net (code "74") (name "TGT_SWCLK") (class "Default")
      (node (ref "IC4") (pin "5") (pinfunction "TCK/SWDCLK_5") (pintype "bidirectional"))
      (node (ref "SV2") (pin "11") (pinfunction "11_11") (pintype "passive"))
    )
    (net (code "75") (name "TGT_SWCLK1") (class "Default")
      (node (ref "IC2") (pin "16") (pinfunction "TGT_SWCLK_16") (pintype "bidirectional"))
      (node (ref "SV2") (pin "12") (pinfunction "12_12") (pintype "passive"))
    )
    (net (code "76") (name "TGT_SWDIO") (class "Default")
      (node (ref "IC4") (pin "3") (pinfunction "TMS/SWDIO_3") (pintype "bidirectional"))
      (node (ref "SV2") (pin "9") (pinfunction "9_9") (pintype "passive"))
    )
    (net (code "77") (name "TGT_SWDIO1") (class "Default")
      (node (ref "IC2") (pin "17") (pinfunction "TGT_SWDIO_17") (pintype "bidirectional"))
      (node (ref "SV2") (pin "10") (pinfunction "10_10") (pintype "passive"))
    )
    (net (code "78") (name "TGT_SWO") (class "Default")
      (node (ref "IC4") (pin "1") (pinfunction "TDO/SWO_1") (pintype "bidirectional"))
      (node (ref "SV2") (pin "7") (pinfunction "7_7") (pintype "passive"))
    )
    (net (code "79") (name "TGT_SWO1") (class "Default")
      (node (ref "IC2") (pin "18") (pinfunction "TGT_SWO_18") (pintype "bidirectional"))
      (node (ref "SV2") (pin "8") (pinfunction "8_8") (pintype "passive"))
    )
    (net (code "80") (name "TGT_TX") (class "Default")
      (node (ref "IC4") (pin "98") (pinfunction "P0.2/TXD0/AD0.7_98") (pintype "bidirectional"))
      (node (ref "SV2") (pin "3") (pinfunction "3_3") (pintype "passive"))
    )
    (net (code "81") (name "TGT_TX1") (class "Default")
      (node (ref "IC2") (pin "31") (pinfunction "TGT_TX_31") (pintype "bidirectional"))
      (node (ref "SV2") (pin "4") (pinfunction "4_4") (pintype "passive"))
    )
    (net (code "82") (name "VBUS_IF") (class "Default")
      (node (ref "C1") (pin "1") (pinfunction "P$1_1") (pintype "passive"))
      (node (ref "CON1") (pin "VBUS") (pinfunction "VBUS_VBUS") (pintype "bidirectional"))
      (node (ref "D2") (pin "A") (pinfunction "A_A") (pintype "passive"))
      (node (ref "IC1") (pin "3") (pinfunction "IN_3") (pintype "input"))
    )
    (net (code "83") (name "VBUS_MIX") (class "Default")
      (node (ref "C11") (pin "1") (pinfunction "P$1_1") (pintype "passive"))
      (node (ref "D1") (pin "K") (pinfunction "K_K") (pintype "passive"))
      (node (ref "D2") (pin "K") (pinfunction "K_K") (pintype "passive"))
      (node (ref "IC3") (pin "3") (pinfunction "IN_3") (pintype "input"))
      (node (ref "SV4") (pin "3") (pinfunction "3_3") (pintype "passive"))
      (node (ref "SV4") (pin "4") (pinfunction "4_4") (pintype "passive"))
    )
    (net (code "84") (name "VBUS_TGT") (class "Default")
      (node (ref "CON2") (pin "VBUS") (pinfunction "VBUS_VBUS") (pintype "bidirectional"))
      (node (ref "D1") (pin "A") (pinfunction "A_A") (pintype "passive"))
    )
    (net (code "85") (name "unconnected-(IC4-P0.0{slash}CAN_RX1{slash}TXD3{slash}SDA1-Pad46)") (class "Default")
      (node (ref "IC4") (pin "46") (pinfunction "P0.0/CAN_RX1/TXD3/SDA1_46") (pintype "bidirectional"))
    )
    (net (code "86") (name "unconnected-(IC4-P0.1{slash}CAN_TX1{slash}RXD3{slash}SCL1-Pad47)") (class "Default")
      (node (ref "IC4") (pin "47") (pinfunction "P0.1/CAN_TX1/RXD3/SCL1_47") (pintype "bidirectional"))
    )
    (net (code "87") (name "unconnected-(IC4-P0.4{slash}I2SRX_CLK{slash}CAN_RX2{slash}CAP2.0-Pad81)") (class "Default")
      (node (ref "IC4") (pin "81") (pinfunction "P0.4/I2SRX_CLK/CAN_RX2/CAP2.0_81") (pintype "bidirectional"))
    )
    (net (code "88") (name "unconnected-(IC4-P0.5{slash}I2SRX_WS{slash}CAN_TX2{slash}CAP2.1-Pad80)") (class "Default")
      (node (ref "IC4") (pin "80") (pinfunction "P0.5/I2SRX_WS/CAN_TX2/CAP2.1_80") (pintype "bidirectional"))
    )
    (net (code "89") (name "unconnected-(IC4-P0.6{slash}I2SRX_SDA{slash}SSEL1{slash}MAT2.0-Pad79)") (class "Default")
      (node (ref "IC4") (pin "79") (pinfunction "P0.6/I2SRX_SDA/SSEL1/MAT2.0_79") (pintype "bidirectional"))
    )
    (net (code "90") (name "unconnected-(IC4-P0.7{slash}I2STX_CLK{slash}SCK1{slash}MAT2.1-Pad78)") (class "Default")
      (node (ref "IC4") (pin "78") (pinfunction "P0.7/I2STX_CLK/SCK1/MAT2.1_78") (pintype "bidirectional"))
    )
    (net (code "91") (name "unconnected-(IC4-P0.8{slash}I2STX_WS{slash}MISO1{slash}MAT2.2-Pad77)") (class "Default")
      (node (ref "IC4") (pin "77") (pinfunction "P0.8/I2STX_WS/MISO1/MAT2.2_77") (pintype "bidirectional"))
    )
    (net (code "92") (name "unconnected-(IC4-P0.9{slash}I2STX_SDA{slash}MOSI1{slash}MAT2.3-Pad76)") (class "Default")
      (node (ref "IC4") (pin "76") (pinfunction "P0.9/I2STX_SDA/MOSI1/MAT2.3_76") (pintype "bidirectional"))
    )
    (net (code "93") (name "unconnected-(IC4-P0.10{slash}TXD2{slash}SDA2{slash}MAT3.0-Pad48)") (class "Default")
      (node (ref "IC4") (pin "48") (pinfunction "P0.10/TXD2/SDA2/MAT3.0_48") (pintype "bidirectional"))
    )
    (net (code "94") (name "unconnected-(IC4-P0.11{slash}RXD2{slash}SCL2{slash}MAT3.1-Pad49)") (class "Default")
      (node (ref "IC4") (pin "49") (pinfunction "P0.11/RXD2/SCL2/MAT3.1_49") (pintype "bidirectional"))
    )
    (net (code "95") (name "unconnected-(IC4-P0.16{slash}RXD1{slash}SSEL0{slash}SSEL-Pad63)") (class "Default")
      (node (ref "IC4") (pin "63") (pinfunction "P0.16/RXD1/SSEL0/SSEL_63") (pintype "bidirectional"))
    )
    (net (code "96") (name "unconnected-(IC4-P0.17{slash}CTS1{slash}MISO0{slash}MISO-Pad61)") (class "Default")
      (node (ref "IC4") (pin "61") (pinfunction "P0.17/CTS1/MISO0/MISO_61") (pintype "bidirectional"))
    )
    (net (code "97") (name "unconnected-(IC4-P0.18{slash}DCD1{slash}MOSI0{slash}MOSI1-Pad60)") (class "Default")
      (node (ref "IC4") (pin "60") (pinfunction "P0.18/DCD1/MOSI0/MOSI1_60") (pintype "bidirectional"))
    )
    (net (code "98") (name "unconnected-(IC4-P0.19{slash}DSR1{slash}MCICLK{slash}SDA1-Pad59)") (class "Default")
      (node (ref "IC4") (pin "59") (pinfunction "P0.19/DSR1/MCICLK/SDA1_59") (pintype "bidirectional"))
    )
    (net (code "99") (name "unconnected-(IC4-P0.20{slash}DTR1{slash}SCL1-Pad58)") (class "Default")
      (node (ref "IC4") (pin "58") (pinfunction "P0.20/DTR1/SCL1_58") (pintype "bidirectional"))
    )
    (net (code "100") (name "unconnected-(IC4-P0.21{slash}RI1{slash}CAN_RX1-Pad57)") (class "Default")
      (node (ref "IC4") (pin "57") (pinfunction "P0.21/RI1/CAN_RX1_57") (pintype "bidirectional"))
    )
    (net (code "101") (name "unconnected-(IC4-P0.22{slash}RTS1{slash}CAN_TX1-Pad56)") (class "Default")
      (node (ref "IC4") (pin "56") (pinfunction "P0.22/RTS1/CAN_TX1_56") (pintype "bidirectional"))
    )
    (net (code "102") (name "unconnected-(IC4-P0.23{slash}AD0.0{slash}I2SRX_CLK{slash}CAP3.0-Pad9)") (class "Default")
      (node (ref "IC4") (pin "9") (pinfunction "P0.23/AD0.0/I2SRX_CLK/CAP3.0_9") (pintype "bidirectional"))
    )
    (net (code "103") (name "unconnected-(IC4-P0.24{slash}AD0.1{slash}I2SRX_WS{slash}CAP3.1-Pad8)") (class "Default")
      (node (ref "IC4") (pin "8") (pinfunction "P0.24/AD0.1/I2SRX_WS/CAP3.1_8") (pintype "bidirectional"))
    )
    (net (code "104") (name "unconnected-(IC4-P0.25{slash}AD0.2{slash}I2SRX_SDA{slash}TXD3-Pad7)") (class "Default")
      (node (ref "IC4") (pin "7") (pinfunction "P0.25/AD0.2/I2SRX_SDA/TXD3_7") (pintype "bidirectional"))
    )
    (net (code "105") (name "unconnected-(IC4-P0.26{slash}AD0.3{slash}AOUT{slash}RXD3-Pad6)") (class "Default")
      (node (ref "IC4") (pin "6") (pinfunction "P0.26/AD0.3/AOUT/RXD3_6") (pintype "bidirectional"))
    )
    (net (code "106") (name "unconnected-(IC4-P0.27{slash}SDA0{slash}USB_SDA-Pad25)") (class "Default")
      (node (ref "IC4") (pin "25") (pinfunction "P0.27/SDA0/USB_SDA_25") (pintype "bidirectional"))
    )
    (net (code "107") (name "unconnected-(IC4-P0.28{slash}SCL0{slash}USB_SCL-Pad24)") (class "Default")
      (node (ref "IC4") (pin "24") (pinfunction "P0.28/SCL0/USB_SCL_24") (pintype "bidirectional"))
    )
    (net (code "108") (name "unconnected-(IC4-P1.18{slash}USB_UP{slash}PWM1.1{slash}CAP1.0-Pad32)") (class "Default")
      (node (ref "IC4") (pin "32") (pinfunction "P1.18/USB_UP/PWM1.1/CAP1.0_32") (pintype "bidirectional"))
    )
    (net (code "109") (name "unconnected-(IC4-P1.19{slash}MC0A{slash}USB_PPWR{slash}CAP1.1-Pad33)") (class "Default")
      (node (ref "IC4") (pin "33") (pinfunction "P1.19/MC0A/USB_PPWR/CAP1.1_33") (pintype "bidirectional"))
    )
    (net (code "110") (name "unconnected-(IC4-P1.20{slash}MCFB0{slash}PWM1.2{slash}SCK0-Pad34)") (class "Default")
      (node (ref "IC4") (pin "34") (pinfunction "P1.20/MCFB0/PWM1.2/SCK0_34") (pintype "bidirectional"))
    )
    (net (code "111") (name "unconnected-(IC4-P1.21{slash}MCABORT{slash}PWM1.3{slash}SSEL0-Pad35)") (class "Default")
      (node (ref "IC4") (pin "35") (pinfunction "P1.21/MCABORT/PWM1.3/SSEL0_35") (pintype "bidirectional"))
    )
    (net (code "112") (name "unconnected-(IC4-P1.22{slash}MC0B{slash}USB_PWRD{slash}MAT1.0-Pad36)") (class "Default")
      (node (ref "IC4") (pin "36") (pinfunction "P1.22/MC0B/USB_PWRD/MAT1.0_36") (pintype "bidirectional"))
    )
    (net (code "113") (name "unconnected-(IC4-P1.23{slash}MCFB1{slash}PWM1.4{slash}MISO0-Pad37)") (class "Default")
      (node (ref "IC4") (pin "37") (pinfunction "P1.23/MCFB1/PWM1.4/MISO0_37") (pintype "bidirectional"))
    )
    (net (code "114") (name "unconnected-(IC4-P1.24{slash}MCFB2{slash}PWM1.5{slash}MOSI0-Pad38)") (class "Default")
      (node (ref "IC4") (pin "38") (pinfunction "P1.24/MCFB2/PWM1.5/MOSI0_38") (pintype "bidirectional"))
    )
    (net (code "115") (name "unconnected-(IC4-P1.29{slash}MC2B{slash}PCAP1.1{slash}MAT0.1-Pad45)") (class "Default")
      (node (ref "IC4") (pin "45") (pinfunction "P1.29/MC2B/PCAP1.1/MAT0.1_45") (pintype "bidirectional"))
    )
    (net (code "116") (name "unconnected-(IC4-P1.30{slash}VBUS{slash}AD0.4-Pad21)") (class "Default")
      (node (ref "IC4") (pin "21") (pinfunction "P1.30/VBUS/AD0.4_21") (pintype "bidirectional"))
    )
    (net (code "117") (name "unconnected-(IC4-P1.31{slash}SCK1{slash}AD0.5-Pad20)") (class "Default")
      (node (ref "IC4") (pin "20") (pinfunction "P1.31/SCK1/AD0.5_20") (pintype "bidirectional"))
    )
    (net (code "118") (name "unconnected-(IC4-P2.8{slash}CAN_TX2{slash}TXD2-Pad65)") (class "Default")
      (node (ref "IC4") (pin "65") (pinfunction "P2.8/CAN_TX2/TXD2_65") (pintype "bidirectional"))
    )
    (net (code "119") (name "unconnected-(IC4-P2.11{slash}EINT1N{slash}I2STX_CLK-Pad52)") (class "Default")
      (node (ref "IC4") (pin "52") (pinfunction "P2.11/EINT1N/I2STX_CLK_52") (pintype "bidirectional"))
    )
    (net (code "120") (name "unconnected-(IC4-P2.12{slash}EINT2N{slash}I2STX_WS-Pad51)") (class "Default")
      (node (ref "IC4") (pin "51") (pinfunction "P2.12/EINT2N/I2STX_WS_51") (pintype "bidirectional"))
    )
    (net (code "121") (name "unconnected-(IC4-P2.13{slash}EINT3N{slash}I2STX_SDA-Pad50)") (class "Default")
      (node (ref "IC4") (pin "50") (pinfunction "P2.13/EINT3N/I2STX_SDA_50") (pintype "bidirectional"))
    )
    (net (code "122") (name "unconnected-(IC4-P3.25{slash}MAT0.0{slash}PWM1.2-Pad27)") (class "Default")
      (node (ref "IC4") (pin "27") (pinfunction "P3.25/MAT0.0/PWM1.2_27") (pintype "bidirectional"))
    )
    (net (code "123") (name "unconnected-(IC4-P3.26{slash}STCLK{slash}MAT0.1{slash}PWM1.3-Pad26)") (class "Default")
      (node (ref "IC4") (pin "26") (pinfunction "P3.26/STCLK/MAT0.1/PWM1.3_26") (pintype "bidirectional"))
    )
    (net (code "124") (name "unconnected-(IC4-P4.28{slash}RX_MCLK{slash}MAT2.0{slash}TXD3-Pad82)") (class "Default")
      (node (ref "IC4") (pin "82") (pinfunction "P4.28/RX_MCLK/MAT2.0/TXD3_82") (pintype "bidirectional"))
    )
    (net (code "125") (name "unconnected-(IC4-P4.29{slash}TX_MCLK{slash}MAT2.1{slash}RXD3-Pad85)") (class "Default")
      (node (ref "IC4") (pin "85") (pinfunction "P4.29/TX_MCLK/MAT2.1/RXD3_85") (pintype "bidirectional"))
    )
    (net (code "126") (name "unconnected-(IC4-RSTOUTN-Pad14)") (class "Default")
      (node (ref "IC4") (pin "14") (pinfunction "RSTOUTN_14") (pintype "bidirectional"))
    )
    (net (code "127") (name "unconnected-(IC4-RTCK-Pad100)") (class "Default")
      (node (ref "IC4") (pin "100") (pinfunction "RTCK_100") (pintype "bidirectional"))
    )
    (net (code "128") (name "unconnected-(IC4-TDI-Pad2)") (class "Default")
      (node (ref "IC4") (pin "2") (pinfunction "TDI_2") (pintype "bidirectional"))
    )
    (net (code "129") (name "unconnected-(IC4-TRST_N-Pad4)") (class "Default")
      (node (ref "IC4") (pin "4") (pinfunction "TRST_N_4") (pintype "bidirectional"))
    )
    (net (code "130") (name "unconnected-(IC4-VBAT-Pad19)") (class "Default")
      (node (ref "IC4") (pin "19") (pinfunction "VBAT_19") (pintype "bidirectional"))
    )
  )
)
